# Power.net
KiCad netlist of a schematic drawn in Altium Designer
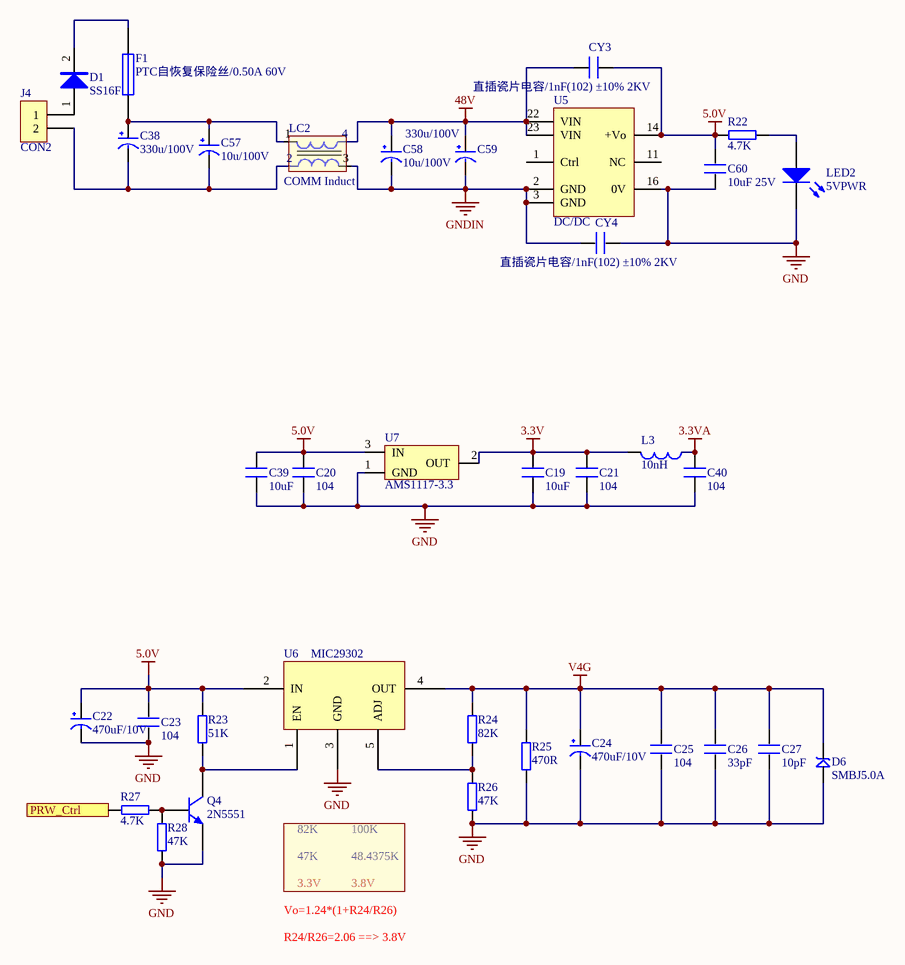
[diagram p0: Power.SchDoc]

(export (version "E")
  (design (tool "Eeschema 10.0.6"))
  (components
    (comp (ref "C19") (value "10uF") (footprint "1206_C") (libsource (lib "CORE") (part "C")))
    (comp (ref "C20") (value "104") (footprint "0603_C") (libsource (lib "CORE") (part "C")))
    (comp (ref "C21") (value "104") (footprint "0603_C") (libsource (lib "CORE") (part "C")))
    (comp (ref "C22") (value "470uF/10V") (footprint "SMD-CT-7343") (libsource (lib "CORE") (part "CAP")))
    (comp (ref "C23") (value "104") (footprint "0603_C") (libsource (lib "CORE") (part "C")))
    (comp (ref "C24") (value "470uF/10V") (footprint "SMD-CT-7343") (libsource (lib "CORE") (part "CAP")))
    (comp (ref "C25") (value "104") (footprint "0603_C") (libsource (lib "CORE") (part "C")))
    (comp (ref "C26") (value "33pF") (footprint "0603_C") (libsource (lib "CORE") (part "C")))
    (comp (ref "C27") (value "10pF") (footprint "0603_C") (libsource (lib "CORE") (part "C")))
    (comp (ref "C38") (value "330u/100V") (footprint "SMD-CT-7343") (libsource (lib "CORE") (part "CAP")))
    (comp (ref "C39") (value "10uF") (footprint "1206_C") (libsource (lib "CORE") (part "C")))
    (comp (ref "C40") (value "104") (footprint "0603_C") (libsource (lib "CORE") (part "C")))
    (comp (ref "C57") (value "10u/100V") (footprint "SMD-CT-7343") (libsource (lib "CORE") (part "CAP")))
    (comp (ref "C58") (value "10u/100V") (footprint "SMD-CT-7343") (libsource (lib "CORE") (part "CAP")))
    (comp (ref "C59") (value "330u/100V") (footprint "SMD-CT-7343") (libsource (lib "CORE") (part "CAP")))
    (comp (ref "C60")
      (value "10uF 25V")
      (footprint "1206_C")
      (description "0805")
      (libsource (lib "CORE") (part "C"))
    )
    (comp (ref "CY3")
      (value "直插瓷片电容/1nF(102) ±10% 2KV")
      (footprint "1206_C")
      (libsource (lib "CORE") (part "C"))
    )
    (comp (ref "CY4")
      (value "直插瓷片电容/1nF(102) ±10% 2KV")
      (footprint "1206_C")
      (libsource (lib "CORE") (part "C"))
    )
    (comp (ref "D1") (value "SS16F") (footprint "SMB(DO-214AA)_S1") (libsource (lib "CORE") (part "SS34")))
    (comp (ref "D6")
      (value "SMBJ5.0A")
      (footprint "SMB(DO-214AA)_S1")
      (description "TVS")
      (libsource (lib "CORE") (part "SMBJ"))
    )
    (comp (ref "F1")
      (value "PTC自恢复保险丝/0.50A 60V")
      (footprint "PIN-W2/E2.8")
      (description "Fuse")
      (fields (field (name "PUBLISHER") "Altium Limited"))
      (libsource (lib "Miscellaneous Devices") (part "Fuse 1"))
    )
    (comp (ref "J4") (value "CON2") (footprint "CON5.08-2P") (libsource (lib "常用元件库") (part "CON2")))
    (comp (ref "L3") (value "10nH") (footprint "0805_L") (libsource (lib "常用元件库") (part "L")))
    (comp (ref "LC2") (value "COMM Induct") (libsource (lib "BatteryIot-V3") (part "FL2D-Z5-103")))
    (comp (ref "LED2")
      (value "5VPWR")
      (footprint "SMDLED")
      (description "Typical RED, GREEN, YELLOW, AMBER GaAs LED")
      (fields (field (name "PUBLISHER") "Altium Limited"))
      (libsource (lib "CORE") (part "LED2"))
    )
    (comp (ref "Q4") (value "2N5551") (footprint "SOT-23") (libsource (lib "PLC1") (part "NPN")))
    (comp (ref "R22") (value "4.7K") (footprint "0603_R") (libsource (lib "EC20-北极芯") (part "RES")))
    (comp (ref "R23") (value "51K") (footprint "0603_R") (libsource (lib "EC20-北极芯") (part "RES")))
    (comp (ref "R24") (value "82K") (footprint "0603_R") (libsource (lib "EC20-北极芯") (part "RES")))
    (comp (ref "R25") (value "470R") (footprint "1206_R") (libsource (lib "EC20-北极芯") (part "RES")))
    (comp (ref "R26") (value "47K") (footprint "0603_R") (libsource (lib "EC20-北极芯") (part "RES")))
    (comp (ref "R27") (value "4.7K") (footprint "0603_R") (libsource (lib "EC20-北极芯") (part "RES")))
    (comp (ref "R28") (value "47K") (footprint "0603_R") (libsource (lib "EC20-北极芯") (part "RES")))
    (comp (ref "U5") (value "DC/DC") (libsource (lib "BatteryIot-V3") (part "VRB4805ZP-10WR3")))
    (comp (ref "U6")
      (value "MIC29302")
      (footprint "TO-263-5-NEW")
      (libsource (lib "EC20-北极芯") (part "MIC29302WU"))
    )
    (comp (ref "U7") (value "AMS1117-3.3") (footprint "SOT-223") (libsource (lib "CORE") (part "AMS1117")))
  )
  (nets
    (net (code "1") (name "/PRW_Ctrl") (class "Default")
      (node (ref "R27") (pin "2") (pinfunction "2_2") (pintype "passive"))
    )
    (net (code "2") (name "3.3V") (class "Default")
      (node (ref "C19") (pin "1") (pintype "passive"))
      (node (ref "C21") (pin "1") (pintype "passive"))
      (node (ref "L3") (pin "1") (pinfunction "1_1") (pintype "passive"))
      (node (ref "U7") (pin "2") (pinfunction "OUT_2") (pintype "passive"))
    )
    (net (code "3") (name "3.3VA") (class "Default")
      (node (ref "C40") (pin "1") (pintype "passive"))
      (node (ref "L3") (pin "2") (pinfunction "2_2") (pintype "passive"))
    )
    (net (code "4") (name "5.0V") (class "Default")
      (node (ref "C20") (pin "1") (pintype "passive"))
      (node (ref "C22") (pin "1") (pinfunction "VCC_1") (pintype "passive"))
      (node (ref "C23") (pin "1") (pintype "passive"))
      (node (ref "C39") (pin "2") (pintype "passive"))
      (node (ref "C60") (pin "1") (pintype "passive"))
      (node (ref "CY3") (pin "2") (pintype "passive"))
      (node (ref "R22") (pin "2") (pinfunction "2_2") (pintype "passive"))
      (node (ref "R23") (pin "2") (pinfunction "2_2") (pintype "passive"))
      (node (ref "U5") (pin "14") (pinfunction "+Vo_14") (pintype "passive"))
      (node (ref "U6") (pin "2") (pinfunction "IN_2") (pintype "passive"))
      (node (ref "U7") (pin "3") (pinfunction "IN_3") (pintype "passive"))
    )
    (net (code "5") (name "48V") (class "Default")
      (node (ref "C58") (pin "1") (pinfunction "VCC_1") (pintype "passive"))
      (node (ref "C59") (pin "1") (pinfunction "VCC_1") (pintype "passive"))
      (node (ref "CY3") (pin "1") (pintype "passive"))
      (node (ref "LC2") (pin "4") (pinfunction "4_4") (pintype "passive"))
      (node (ref "U5") (pin "22") (pinfunction "VIN_22") (pintype "passive"))
      (node (ref "U5") (pin "23") (pinfunction "VIN_23") (pintype "passive"))
    )
    (net (code "6") (name "GND") (class "Default")
      (node (ref "C19") (pin "2") (pintype "passive"))
      (node (ref "C20") (pin "2") (pintype "passive"))
      (node (ref "C21") (pin "2") (pintype "passive"))
      (node (ref "C22") (pin "2") (pinfunction "GND_2") (pintype "passive"))
      (node (ref "C23") (pin "2") (pintype "passive"))
      (node (ref "C24") (pin "2") (pinfunction "GND_2") (pintype "passive"))
      (node (ref "C25") (pin "2") (pintype "passive"))
      (node (ref "C26") (pin "2") (pintype "passive"))
      (node (ref "C27") (pin "2") (pintype "passive"))
      (node (ref "C39") (pin "1") (pintype "passive"))
      (node (ref "C40") (pin "2") (pintype "passive"))
      (node (ref "C60") (pin "2") (pintype "passive"))
      (node (ref "CY4") (pin "2") (pintype "passive"))
      (node (ref "D6") (pin "1") (pintype "passive"))
      (node (ref "LED2") (pin "2") (pinfunction "K_2") (pintype "passive"))
      (node (ref "Q4") (pin "2") (pinfunction "2_2") (pintype "passive"))
      (node (ref "R25") (pin "1") (pinfunction "1_1") (pintype "passive"))
      (node (ref "R26") (pin "1") (pinfunction "1_1") (pintype "passive"))
      (node (ref "R28") (pin "1") (pinfunction "1_1") (pintype "passive"))
      (node (ref "U5") (pin "16") (pinfunction "0V_16") (pintype "passive"))
      (node (ref "U6") (pin "3") (pinfunction "GND_3") (pintype "passive"))
      (node (ref "U7") (pin "1") (pinfunction "GND_1") (pintype "passive"))
    )
    (net (code "7") (name "GNDIN") (class "Default")
      (node (ref "C58") (pin "2") (pinfunction "GND_2") (pintype "passive"))
      (node (ref "C59") (pin "2") (pinfunction "GND_2") (pintype "passive"))
      (node (ref "CY4") (pin "1") (pintype "passive"))
      (node (ref "LC2") (pin "3") (pinfunction "3_3") (pintype "passive"))
      (node (ref "U5") (pin "2") (pinfunction "GND_2") (pintype "passive"))
      (node (ref "U5") (pin "3") (pinfunction "GND_3") (pintype "passive"))
    )
    (net (code "8") (name "Net-(C38-GND)") (class "Default")
      (node (ref "C38") (pin "2") (pinfunction "GND_2") (pintype "passive"))
      (node (ref "C57") (pin "2") (pinfunction "GND_2") (pintype "passive"))
      (node (ref "J4") (pin "2") (pinfunction "2_2") (pintype "passive"))
      (node (ref "LC2") (pin "2") (pinfunction "2_2") (pintype "passive"))
    )
    (net (code "9") (name "Net-(C38-VCC)") (class "Default")
      (node (ref "C38") (pin "1") (pinfunction "VCC_1") (pintype "passive"))
      (node (ref "C57") (pin "1") (pinfunction "VCC_1") (pintype "passive"))
      (node (ref "F1") (pin "1") (pinfunction "1_1") (pintype "passive"))
      (node (ref "LC2") (pin "1") (pinfunction "1_1") (pintype "passive"))
    )
    (net (code "10") (name "Net-(D1-Pad1)") (class "Default")
      (node (ref "D1") (pin "1") (pinfunction "1_1") (pintype "passive"))
      (node (ref "J4") (pin "1") (pinfunction "1_1") (pintype "passive"))
    )
    (net (code "11") (name "Net-(D1-Pad2)") (class "Default")
      (node (ref "D1") (pin "2") (pinfunction "2_2") (pintype "passive"))
      (node (ref "F1") (pin "2") (pinfunction "2_2") (pintype "passive"))
    )
    (net (code "12") (name "Net-(LED2-A)") (class "Default")
      (node (ref "LED2") (pin "1") (pinfunction "A_1") (pintype "passive"))
      (node (ref "R22") (pin "1") (pinfunction "1_1") (pintype "passive"))
    )
    (net (code "13") (name "Net-(Q4-Pad1)") (class "Default")
      (node (ref "Q4") (pin "1") (pinfunction "1_1") (pintype "passive"))
      (node (ref "R27") (pin "1") (pinfunction "1_1") (pintype "passive"))
      (node (ref "R28") (pin "2") (pinfunction "2_2") (pintype "passive"))
    )
    (net (code "14") (name "Net-(U6-ADJ)") (class "Default")
      (node (ref "R24") (pin "1") (pinfunction "1_1") (pintype "passive"))
      (node (ref "R26") (pin "2") (pinfunction "2_2") (pintype "passive"))
      (node (ref "U6") (pin "5") (pinfunction "ADJ_5") (pintype "passive"))
    )
    (net (code "15") (name "Net-(U6-EN)") (class "Default")
      (node (ref "Q4") (pin "3") (pinfunction "3_3") (pintype "passive"))
      (node (ref "R23") (pin "1") (pinfunction "1_1") (pintype "passive"))
      (node (ref "U6") (pin "1") (pinfunction "EN_1") (pintype "passive"))
    )
    (net (code "16") (name "V4G") (class "Default")
      (node (ref "C24") (pin "1") (pinfunction "VCC_1") (pintype "passive"))
      (node (ref "C25") (pin "1") (pintype "passive"))
      (node (ref "C26") (pin "1") (pintype "passive"))
      (node (ref "C27") (pin "1") (pintype "passive"))
      (node (ref "D6") (pin "2") (pintype "passive"))
      (node (ref "R24") (pin "2") (pinfunction "2_2") (pintype "passive"))
      (node (ref "R25") (pin "2") (pinfunction "2_2") (pintype "passive"))
      (node (ref "U6") (pin "4") (pinfunction "OUT_4") (pintype "passive"))
    )
    (net (code "17") (name "unconnected-(U5-Ctrl-Pad1)") (class "Default")
      (node (ref "U5") (pin "1") (pinfunction "Ctrl_1") (pintype "passive"))
    )
    (net (code "18") (name "unconnected-(U5-NC-Pad11)") (class "Default")
      (node (ref "U5") (pin "11") (pinfunction "NC_11") (pintype "passive"))
    )
  )
)
